# Heartrate_Monitor_External.net
KiCad netlist of a schematic drawn in Altium Designer
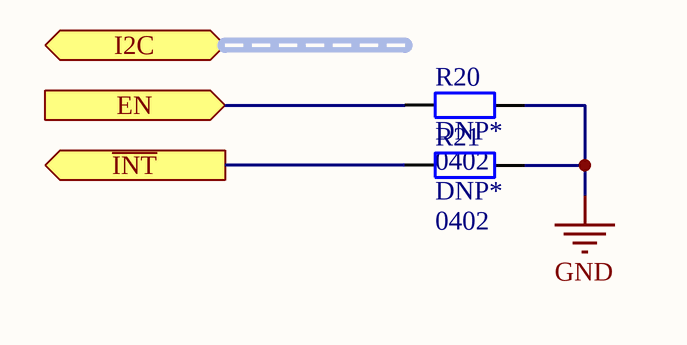
[diagram p0: Heartrate_Monitor_External.SchDoc]

(export (version "E")
  (design (tool "Eeschema 10.0.6"))
  (components
    (comp (ref "R20")
      (value "DNP*")
      (footprint "0402R")
      (description "Placeholder for a 0402 resistor")
      (fields (field (name "CASE/PACKAGE") "0402"))
      (libsource (lib "resistors_smd") (part "RES SMD NO BOM 0402"))
    )
    (comp (ref "R21")
      (value "DNP*")
      (footprint "0402R")
      (description "Placeholder for a 0402 resistor")
      (fields (field (name "CASE/PACKAGE") "0402"))
      (libsource (lib "resistors_smd") (part "RES SMD NO BOM 0402"))
    )
  )
  (nets
    (net (code "2") (name "/EN") (class "Default")
      (node (ref "R20") (pin "2") (pinfunction "2_2") (pintype "passive"))
    )
    (net (code "4") (name "/INT") (class "Default")
      (node (ref "R21") (pin "2") (pinfunction "2_2") (pintype "passive"))
    )
    (net (code "5") (name "GND") (class "Default")
      (node (ref "R20") (pin "1") (pinfunction "1_1") (pintype "passive"))
      (node (ref "R21") (pin "1") (pinfunction "1_1") (pintype "passive"))
    )
  )
)
